# M5stamp_round_lcd.net
KiCad netlist of a schematic drawn in EAGLE
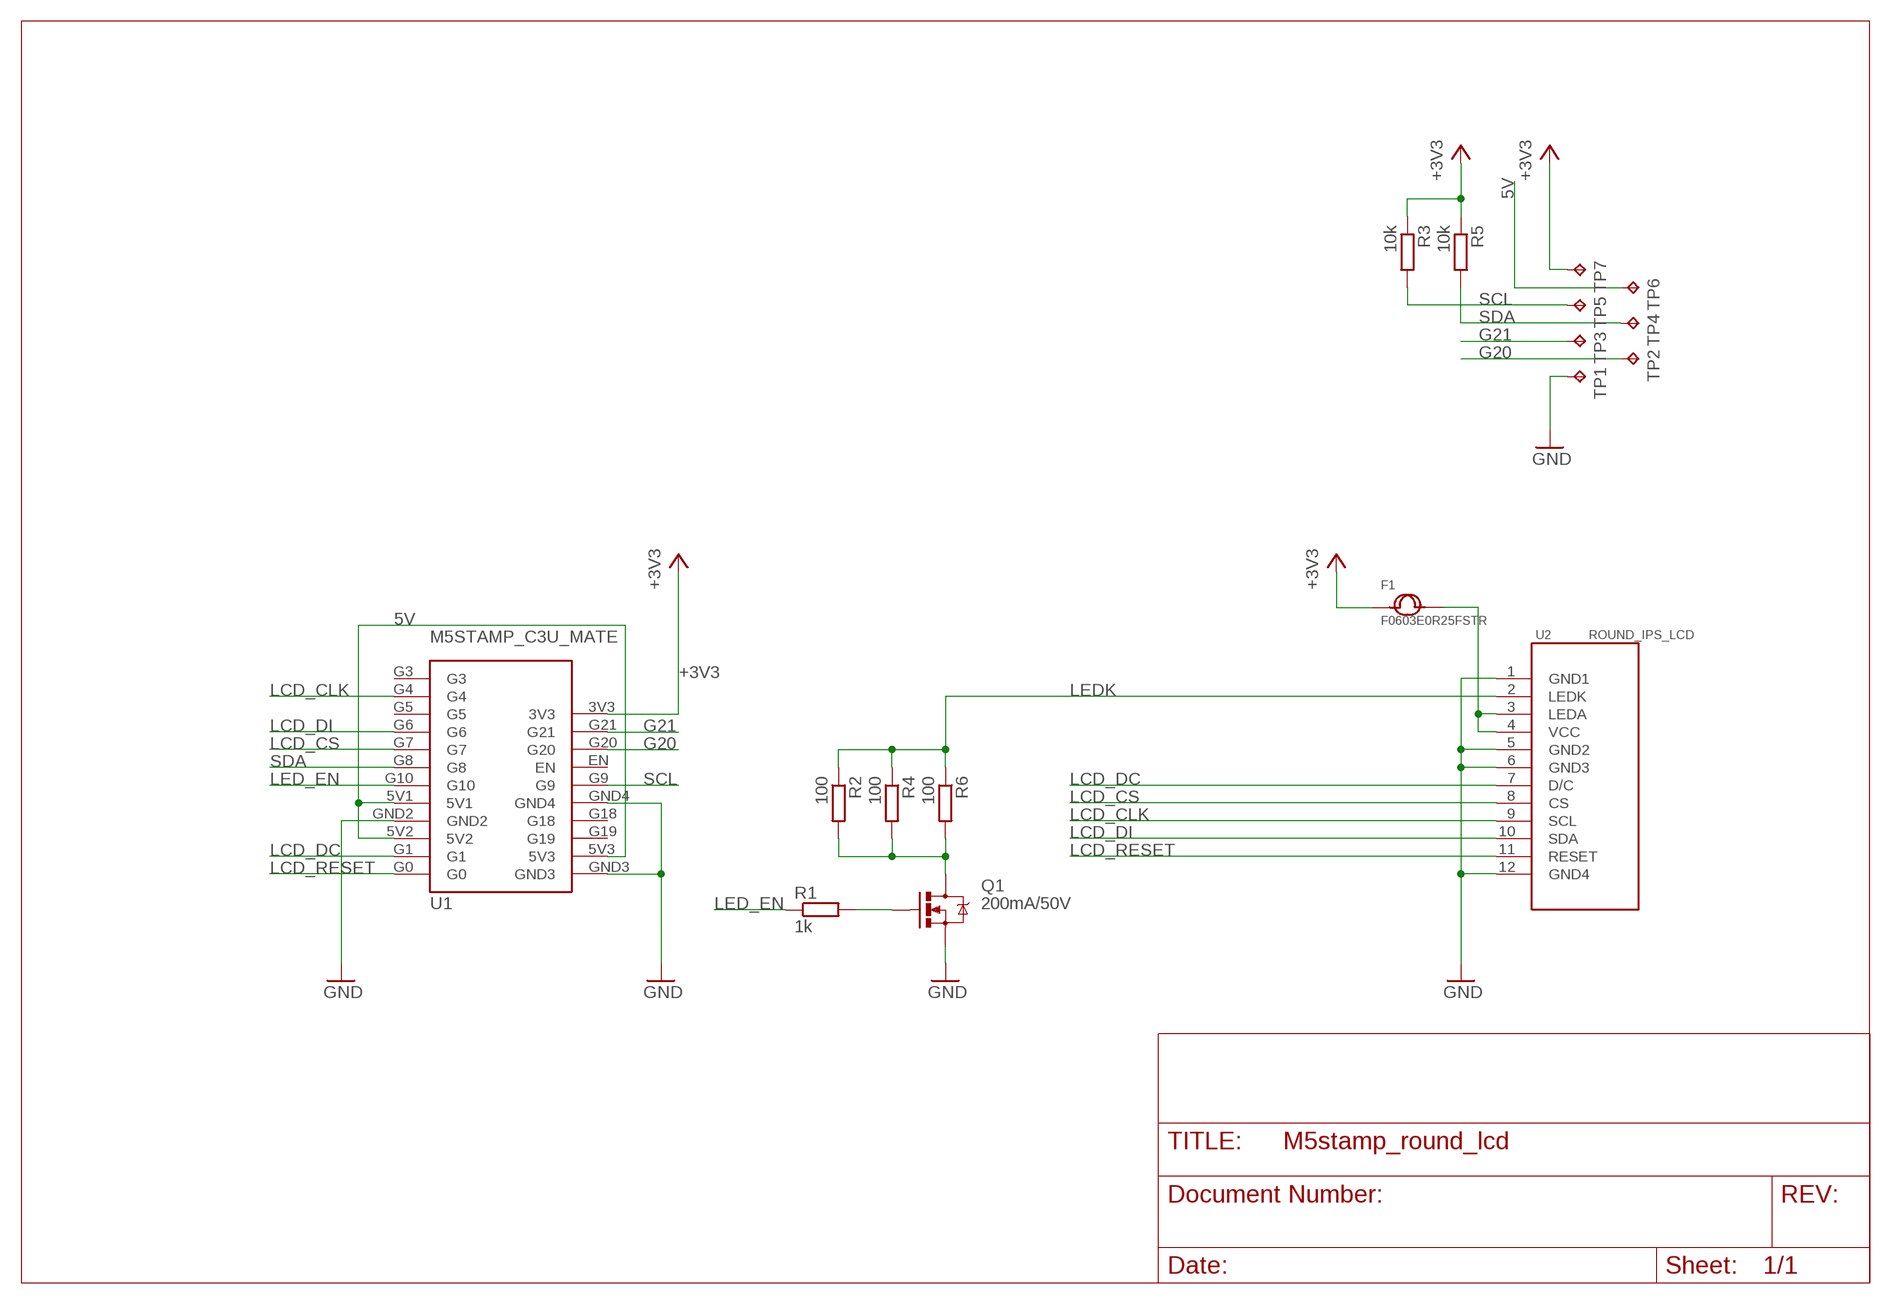
[diagram p0: schematic, sheet 1]

(export (version "E")
  (design (tool "Eeschema 10.0.6"))
  (components
    (comp (ref "F1")
      (value "F0603E0R25FSTR")
      (footprint "eagle-import:C0603")
      (libsource (lib "eagle-import") (part "FUSE0603"))
    )
    (comp (ref "Q1")
      (value "200mA/50V")
      (footprint "eagle-import:SOT23-3")
      (libsource (lib "eagle-import") (part "MOSFET-NCHANNELBSS138"))
    )
    (comp (ref "R1")
      (value "1k")
      (footprint "eagle-import:R0603")
      (libsource (lib "eagle-import") (part "R-EU_R0603"))
    )
    (comp (ref "R2")
      (value "100")
      (footprint "eagle-import:R0603")
      (libsource (lib "eagle-import") (part "R-EU_R0603"))
    )
    (comp (ref "R3")
      (value "10k")
      (footprint "eagle-import:R0603")
      (libsource (lib "eagle-import") (part "R-EU_R0603"))
    )
    (comp (ref "R4")
      (value "100")
      (footprint "eagle-import:R0603")
      (libsource (lib "eagle-import") (part "R-EU_R0603"))
    )
    (comp (ref "R5")
      (value "10k")
      (footprint "eagle-import:R0603")
      (libsource (lib "eagle-import") (part "R-EU_R0603"))
    )
    (comp (ref "R6")
      (value "100")
      (footprint "eagle-import:R0603")
      (libsource (lib "eagle-import") (part "R-EU_R0603"))
    )
    (comp (ref "TP1")
      (value "TPTP18R")
      (footprint "eagle-import:TP18R")
      (libsource (lib "eagle-import") (part "TPTP18R"))
    )
    (comp (ref "TP2")
      (value "TPTP18R")
      (footprint "eagle-import:TP18R")
      (libsource (lib "eagle-import") (part "TPTP18R"))
    )
    (comp (ref "TP3")
      (value "TPTP18R")
      (footprint "eagle-import:TP18R")
      (libsource (lib "eagle-import") (part "TPTP18R"))
    )
    (comp (ref "TP4")
      (value "TPTP18R")
      (footprint "eagle-import:TP18R")
      (libsource (lib "eagle-import") (part "TPTP18R"))
    )
    (comp (ref "TP5")
      (value "TPTP18R")
      (footprint "eagle-import:TP18R")
      (libsource (lib "eagle-import") (part "TPTP18R"))
    )
    (comp (ref "TP6")
      (value "TPTP18R")
      (footprint "eagle-import:TP18R")
      (libsource (lib "eagle-import") (part "TPTP18R"))
    )
    (comp (ref "TP7")
      (value "TPTP18R")
      (footprint "eagle-import:TP18R")
      (libsource (lib "eagle-import") (part "TPTP18R"))
    )
    (comp (ref "U1")
      (value "M5STAMP_C3U_MATE")
      (footprint "eagle-import:M5STAMPC3UMATE")
      (libsource (lib "eagle-import") (part "M5STAMP_C3U_MATE"))
    )
    (comp (ref "U2")
      (value "ROUND_IPS_LCD")
      (footprint "eagle-import:ROUND_IPS_LCD")
      (libsource (lib "eagle-import") (part "ROUND_IPS_LCD"))
    )
  )
  (nets
    (net (code "1") (name "+3V3") (class "Default")
      (node (ref "F1") (pin "1") (pinfunction "1_1") (pintype "bidirectional"))
      (node (ref "R3") (pin "1") (pinfunction "1_1") (pintype "passive"))
      (node (ref "R5") (pin "1") (pinfunction "1_1") (pintype "passive"))
      (node (ref "TP7") (pin "TP") (pinfunction "TP_TP") (pintype "input"))
      (node (ref "U1") (pin "3V3") (pinfunction "3V3_3V3") (pintype "bidirectional"))
    )
    (net (code "2") (name "/5V") (class "Default")
      (node (ref "TP6") (pin "TP") (pinfunction "TP_TP") (pintype "input"))
      (node (ref "U1") (pin "5V1") (pinfunction "5V1_5V1") (pintype "bidirectional"))
      (node (ref "U1") (pin "5V2") (pinfunction "5V2_5V2") (pintype "bidirectional"))
      (node (ref "U1") (pin "5V3") (pinfunction "5V3_5V3") (pintype "bidirectional"))
    )
    (net (code "3") (name "/G20") (class "Default")
      (node (ref "TP2") (pin "TP") (pinfunction "TP_TP") (pintype "input"))
      (node (ref "U1") (pin "G20") (pinfunction "G20_G20") (pintype "bidirectional"))
    )
    (net (code "4") (name "/G21") (class "Default")
      (node (ref "TP3") (pin "TP") (pinfunction "TP_TP") (pintype "input"))
      (node (ref "U1") (pin "G21") (pinfunction "G21_G21") (pintype "bidirectional"))
    )
    (net (code "5") (name "/LCD_CLK") (class "Default")
      (node (ref "U1") (pin "G4") (pinfunction "G4_G4") (pintype "bidirectional"))
      (node (ref "U2") (pin "9") (pinfunction "SCL_9") (pintype "input"))
    )
    (net (code "6") (name "/LCD_CS") (class "Default")
      (node (ref "U1") (pin "G7") (pinfunction "G7_G7") (pintype "bidirectional"))
      (node (ref "U2") (pin "8") (pinfunction "CS_8") (pintype "input"))
    )
    (net (code "7") (name "/LCD_DC") (class "Default")
      (node (ref "U1") (pin "G1") (pinfunction "G1_G1") (pintype "bidirectional"))
      (node (ref "U2") (pin "7") (pinfunction "D/C_7") (pintype "input"))
    )
    (net (code "8") (name "/LCD_DI") (class "Default")
      (node (ref "U1") (pin "G6") (pinfunction "G6_G6") (pintype "bidirectional"))
      (node (ref "U2") (pin "10") (pinfunction "SDA_10") (pintype "bidirectional"))
    )
    (net (code "9") (name "/LCD_RESET") (class "Default")
      (node (ref "U1") (pin "G0") (pinfunction "G0_G0") (pintype "bidirectional"))
      (node (ref "U2") (pin "11") (pinfunction "RESET_11") (pintype "input"))
    )
    (net (code "10") (name "/LEDK") (class "Default")
      (node (ref "R2") (pin "1") (pinfunction "1_1") (pintype "passive"))
      (node (ref "R4") (pin "1") (pinfunction "1_1") (pintype "passive"))
      (node (ref "R6") (pin "1") (pinfunction "1_1") (pintype "passive"))
      (node (ref "U2") (pin "2") (pinfunction "LEDK_2") (pintype "bidirectional"))
    )
    (net (code "11") (name "/LED_EN") (class "Default")
      (node (ref "R1") (pin "1") (pinfunction "1_1") (pintype "passive"))
      (node (ref "U1") (pin "G10") (pinfunction "G10_G10") (pintype "bidirectional"))
    )
    (net (code "12") (name "/SCL") (class "Default")
      (node (ref "R3") (pin "2") (pinfunction "2_2") (pintype "passive"))
      (node (ref "TP5") (pin "TP") (pinfunction "TP_TP") (pintype "input"))
      (node (ref "U1") (pin "G9") (pinfunction "G9_G9") (pintype "bidirectional"))
    )
    (net (code "13") (name "/SDA") (class "Default")
      (node (ref "R5") (pin "2") (pinfunction "2_2") (pintype "passive"))
      (node (ref "TP4") (pin "TP") (pinfunction "TP_TP") (pintype "input"))
      (node (ref "U1") (pin "G8") (pinfunction "G8_G8") (pintype "bidirectional"))
    )
    (net (code "14") (name "GND") (class "Default")
      (node (ref "Q1") (pin "2") (pinfunction "S_2") (pintype "passive"))
      (node (ref "TP1") (pin "TP") (pinfunction "TP_TP") (pintype "input"))
      (node (ref "U1") (pin "GND2") (pinfunction "GND2_GND2") (pintype "bidirectional"))
      (node (ref "U1") (pin "GND3") (pinfunction "GND3_GND3") (pintype "bidirectional"))
      (node (ref "U1") (pin "GND4") (pinfunction "GND4_GND4") (pintype "bidirectional"))
      (node (ref "U2") (pin "1") (pinfunction "GND1_1") (pintype "power_in"))
      (node (ref "U2") (pin "12") (pinfunction "GND4_12") (pintype "power_in"))
      (node (ref "U2") (pin "5") (pinfunction "GND2_5") (pintype "power_in"))
      (node (ref "U2") (pin "6") (pinfunction "GND3_6") (pintype "power_in"))
    )
    (net (code "15") (name "Net-(Q1-D)") (class "Default")
      (node (ref "Q1") (pin "3") (pinfunction "D_3") (pintype "passive"))
      (node (ref "R2") (pin "2") (pinfunction "2_2") (pintype "passive"))
      (node (ref "R4") (pin "2") (pinfunction "2_2") (pintype "passive"))
      (node (ref "R6") (pin "2") (pinfunction "2_2") (pintype "passive"))
    )
    (net (code "16") (name "Net-(Q1-G)") (class "Default")
      (node (ref "Q1") (pin "1") (pinfunction "G_1") (pintype "passive"))
      (node (ref "R1") (pin "2") (pinfunction "2_2") (pintype "passive"))
    )
    (net (code "17") (name "Net-(U2-LEDA)") (class "Default")
      (node (ref "F1") (pin "2") (pinfunction "2_2") (pintype "bidirectional"))
      (node (ref "U2") (pin "3") (pinfunction "LEDA_3") (pintype "bidirectional"))
      (node (ref "U2") (pin "4") (pinfunction "VCC_4") (pintype "power_in"))
    )
    (net (code "18") (name "unconnected-(U1-PadEN)") (class "Default")
      (node (ref "U1") (pin "EN") (pinfunction "EN_EN") (pintype "bidirectional"))
    )
    (net (code "19") (name "unconnected-(U1-PadG3)") (class "Default")
      (node (ref "U1") (pin "G3") (pinfunction "G3_G3") (pintype "bidirectional"))
    )
    (net (code "20") (name "unconnected-(U1-PadG5)") (class "Default")
      (node (ref "U1") (pin "G5") (pinfunction "G5_G5") (pintype "bidirectional"))
    )
    (net (code "21") (name "unconnected-(U1-PadG18)") (class "Default")
      (node (ref "U1") (pin "G18") (pinfunction "G18_G18") (pintype "bidirectional"))
    )
    (net (code "22") (name "unconnected-(U1-PadG19)") (class "Default")
      (node (ref "U1") (pin "G19") (pinfunction "G19_G19") (pintype "bidirectional"))
    )
  )
)
